# shiftRegister.net
KiCad netlist of a schematic drawn in Altium Designer
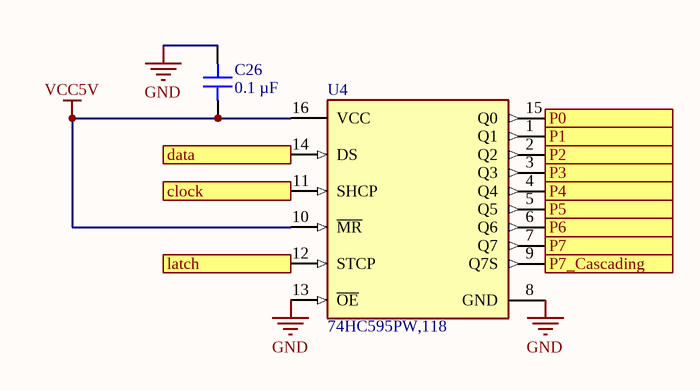
[diagram p0: shiftRegister.SchDoc]

(export (version "E")
  (design (tool "Eeschema 10.0.6"))
  (components
    (comp (ref "C26")
      (value "0.1 µF")
      (footprint "CAP 0603_1608")
      (description "CAP CER 0.1UF 50V X7R 0603")
      (fields (field (name "PART NUMBER") "C0603C104K5RAC7411") (field (name "MANUFACTURER") "KEMET"))
      (libsource (lib "Celestial Altium Library - altium_library") (part "Capacitor"))
    )
    (comp (ref "U4")
      (value "74HC595PW,118")
      (footprint "FP-SOT403-1-MFG")
      (description "IC SHIFT REGISTER 8BIT 16TSSOP")
      (libsource (lib "Altium Content Vault") (part "27683e23285b137cd268a0f18c66bed"))
    )
  )
  (nets
    (net (code "1") (name "/P0") (class "Default")
      (node (ref "U4") (pin "15") (pinfunction "Q0_15") (pintype "output"))
    )
    (net (code "2") (name "/P1") (class "Default")
      (node (ref "U4") (pin "1") (pinfunction "Q1_1") (pintype "output"))
    )
    (net (code "3") (name "/P2") (class "Default")
      (node (ref "U4") (pin "2") (pinfunction "Q2_2") (pintype "output"))
    )
    (net (code "4") (name "/P3") (class "Default")
      (node (ref "U4") (pin "3") (pinfunction "Q3_3") (pintype "output"))
    )
    (net (code "5") (name "/P4") (class "Default")
      (node (ref "U4") (pin "4") (pinfunction "Q4_4") (pintype "output"))
    )
    (net (code "6") (name "/P5") (class "Default")
      (node (ref "U4") (pin "5") (pinfunction "Q5_5") (pintype "output"))
    )
    (net (code "7") (name "/P6") (class "Default")
      (node (ref "U4") (pin "6") (pinfunction "Q6_6") (pintype "output"))
    )
    (net (code "8") (name "/P7") (class "Default")
      (node (ref "U4") (pin "7") (pinfunction "Q7_7") (pintype "output"))
    )
    (net (code "9") (name "/P7_Cascading") (class "Default")
      (node (ref "U4") (pin "9") (pinfunction "Q7S_9") (pintype "output"))
    )
    (net (code "10") (name "/clock") (class "Default")
      (node (ref "U4") (pin "11") (pinfunction "SHCP_11") (pintype "input"))
    )
    (net (code "11") (name "/data") (class "Default")
      (node (ref "U4") (pin "14") (pinfunction "DS_14") (pintype "input"))
    )
    (net (code "12") (name "/latch") (class "Default")
      (node (ref "U4") (pin "12") (pinfunction "STCP_12") (pintype "input"))
    )
    (net (code "13") (name "GND") (class "Default")
      (node (ref "C26") (pin "2") (pinfunction "2_2") (pintype "passive"))
      (node (ref "U4") (pin "13") (pinfunction "~{OE}_13") (pintype "input"))
      (node (ref "U4") (pin "8") (pinfunction "GND_8") (pintype "power_in"))
    )
    (net (code "14") (name "VCC5V") (class "Default")
      (node (ref "C26") (pin "1") (pinfunction "1_1") (pintype "passive"))
      (node (ref "U4") (pin "10") (pinfunction "~{MR}_10") (pintype "input"))
      (node (ref "U4") (pin "16") (pinfunction "VCC_16") (pintype "power_in"))
    )
  )
)
